# satellites_pcb_v2_0.net
KiCad netlist of a schematic drawn in EAGLE
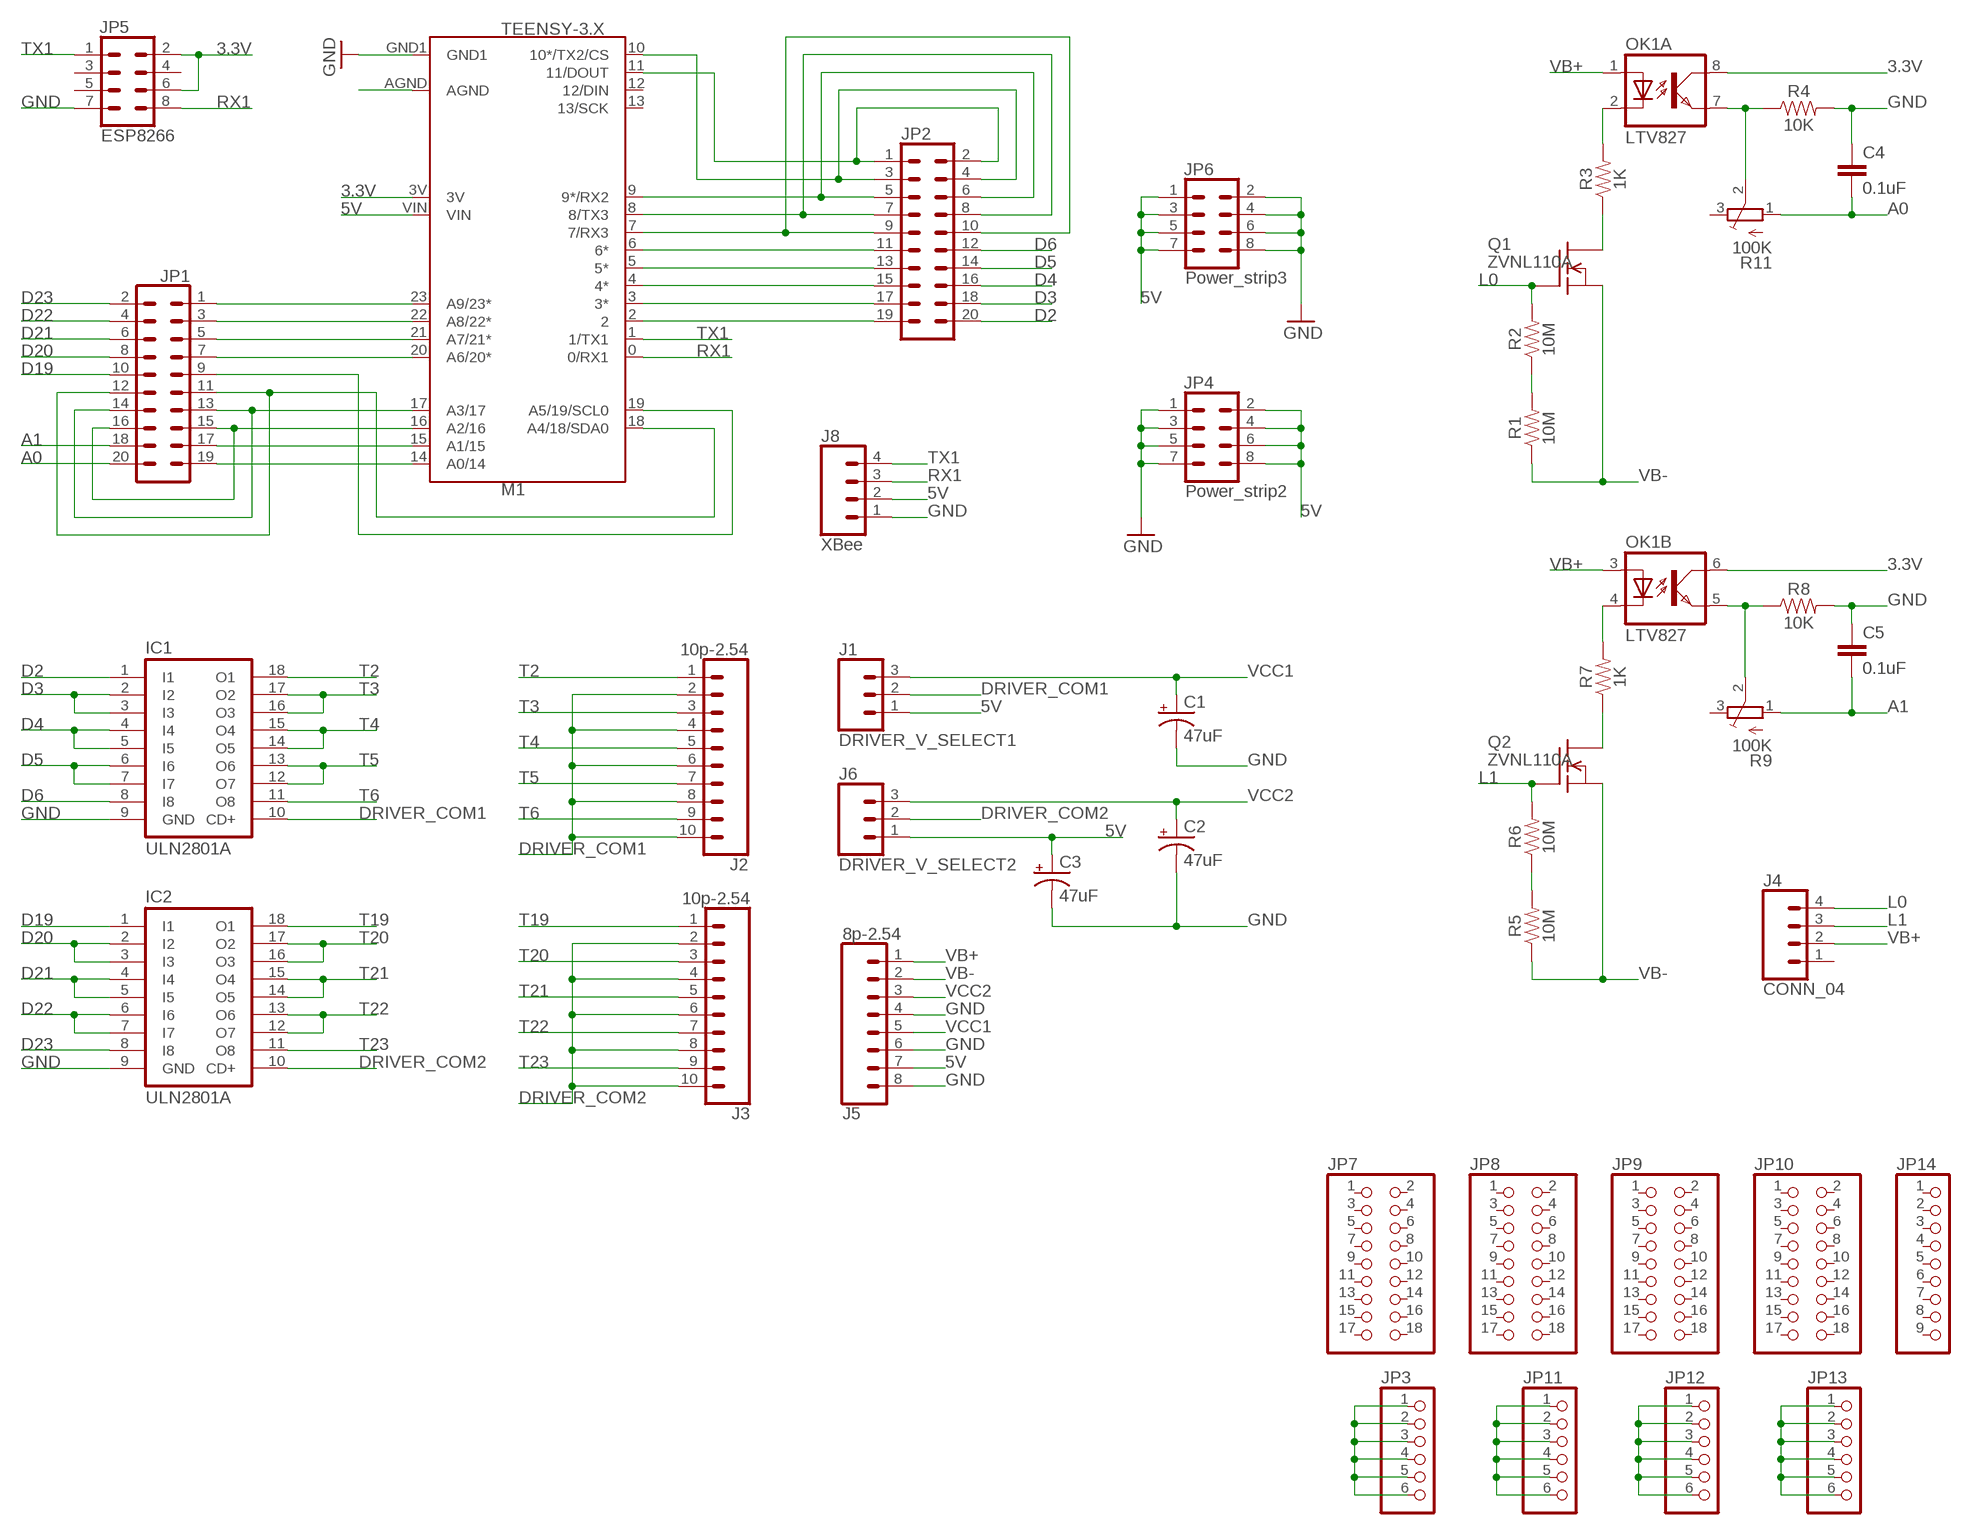
[diagram p0: schematic, sheet 1]

(export (version "E")
  (design (tool "Eeschema 10.0.6"))
  (components
    (comp (ref "C1")
      (value "47uF")
      (footprint "eagle-import:CPOL-RADIAL-2.5MM-6.5MM")
      (libsource (lib "eagle-import") (part "100UF-POLAR-RADIAL-2.5MM-25V-20%"))
    )
    (comp (ref "C2")
      (value "47uF")
      (footprint "eagle-import:CPOL-RADIAL-2.5MM-6.5MM")
      (libsource (lib "eagle-import") (part "100UF-POLAR-RADIAL-2.5MM-25V-20%"))
    )
    (comp (ref "C3")
      (value "47uF")
      (footprint "eagle-import:CPOL-RADIAL-2.5MM-6.5MM")
      (libsource (lib "eagle-import") (part "100UF-POLAR-RADIAL-2.5MM-25V-20%"))
    )
    (comp (ref "C4")
      (value "0.1uF")
      (footprint "eagle-import:CAP-PTH-2.54")
      (libsource (lib "eagle-import") (part "22PF-PTH-2.54MM-200V-5%"))
    )
    (comp (ref "C5")
      (value "0.1uF")
      (footprint "eagle-import:CAP-PTH-2.54")
      (libsource (lib "eagle-import") (part "22PF-PTH-2.54MM-200V-5%"))
    )
    (comp (ref "IC1")
      (value "ULN2801A")
      (footprint "eagle-import:DIL18")
      (libsource (lib "eagle-import") (part "ULN2801A"))
    )
    (comp (ref "IC2")
      (value "ULN2801A")
      (footprint "eagle-import:DIL18")
      (libsource (lib "eagle-import") (part "ULN2801A"))
    )
    (comp (ref "J1")
      (value "DRIVER_V_SELECT1")
      (footprint "eagle-import:1X03_LOCK")
      (libsource (lib "eagle-import") (part "CONN_03LOCK"))
    )
    (comp (ref "J2")
      (value "10p-2.54")
      (footprint "eagle-import:SCREW_TERMINAL_10P_2.54MM_LONGPAD")
      (libsource (lib "eagle-import") (part "CONN_10"))
    )
    (comp (ref "J3")
      (value "10p-2.54")
      (footprint "eagle-import:SCREW_TERMINAL_10P_2.54MM_LONGPAD")
      (libsource (lib "eagle-import") (part "CONN_10"))
    )
    (comp (ref "J4")
      (value "CONN_04")
      (footprint "eagle-import:SCREW_TERMINAL_4P_2.54MM")
      (libsource (lib "eagle-import") (part "CONN_04"))
    )
    (comp (ref "J5")
      (value "8p-2.54")
      (footprint "eagle-import:SCREW_TERMINAL_8P_2.54MM_LONGPAD")
      (libsource (lib "eagle-import") (part "CONN_08SCREW_TERMINAL_8P_2.54MM_LONGPAD"))
    )
    (comp (ref "J6")
      (value "DRIVER_V_SELECT2")
      (footprint "eagle-import:1X03_LOCK")
      (libsource (lib "eagle-import") (part "CONN_03LOCK"))
    )
    (comp (ref "J8")
      (value "XBee")
      (footprint "eagle-import:1X04_LOCK")
      (libsource (lib "eagle-import") (part "CONN_04LOCK"))
    )
    (comp (ref "JP1")
      (value "CONN_10X2")
      (footprint "eagle-import:2X10")
      (libsource (lib "eagle-import") (part "CONN_10X2"))
    )
    (comp (ref "JP2")
      (value "CONN_10X2")
      (footprint "eagle-import:2X10")
      (libsource (lib "eagle-import") (part "CONN_10X2"))
    )
    (comp (ref "JP3")
      (value "PINHD-1X6CLEAN")
      (footprint "eagle-import:1X06-CLEAN")
      (libsource (lib "eagle-import") (part "PINHD-1X6CLEAN"))
    )
    (comp (ref "JP4")
      (value "Power_strip2")
      (footprint "eagle-import:2X4")
      (libsource (lib "eagle-import") (part "CONN_04X2"))
    )
    (comp (ref "JP5")
      (value "ESP8266")
      (footprint "eagle-import:2X4")
      (libsource (lib "eagle-import") (part "CONN_04X2"))
    )
    (comp (ref "JP6")
      (value "Power_strip3")
      (footprint "eagle-import:2X4")
      (libsource (lib "eagle-import") (part "CONN_04X2"))
    )
    (comp (ref "JP7")
      (value "PINHD-2X9-CBIG")
      (footprint "eagle-import:2X09-CLEANBIG")
      (libsource (lib "eagle-import") (part "PINHD-2X9-CBIG"))
    )
    (comp (ref "JP8")
      (value "PINHD-2X9-CBIG")
      (footprint "eagle-import:2X09-CLEANBIG")
      (libsource (lib "eagle-import") (part "PINHD-2X9-CBIG"))
    )
    (comp (ref "JP9")
      (value "PINHD-2X9-CBIG")
      (footprint "eagle-import:2X09-CLEANBIG")
      (libsource (lib "eagle-import") (part "PINHD-2X9-CBIG"))
    )
    (comp (ref "JP10")
      (value "PINHD-2X9-CBIG")
      (footprint "eagle-import:2X09-CLEANBIG")
      (libsource (lib "eagle-import") (part "PINHD-2X9-CBIG"))
    )
    (comp (ref "JP11")
      (value "PINHD-1X6CLEAN")
      (footprint "eagle-import:1X06-CLEAN")
      (libsource (lib "eagle-import") (part "PINHD-1X6CLEAN"))
    )
    (comp (ref "JP12")
      (value "PINHD-1X6CLEAN")
      (footprint "eagle-import:1X06-CLEAN")
      (libsource (lib "eagle-import") (part "PINHD-1X6CLEAN"))
    )
    (comp (ref "JP13")
      (value "PINHD-1X6CLEAN")
      (footprint "eagle-import:1X06-CLEAN")
      (libsource (lib "eagle-import") (part "PINHD-1X6CLEAN"))
    )
    (comp (ref "JP14")
      (value "PINHD-1X9")
      (footprint "eagle-import:1X09-BIG")
      (libsource (lib "eagle-import") (part "PINHD-1X9"))
    )
    (comp (ref "M1")
      (value "TEENSY-3.X")
      (footprint "eagle-import:TEENSY-3.1_NOSILK")
      (libsource (lib "eagle-import") (part "TEENSY-3.1-TWO_ROWSNOSILK"))
    )
    (comp (ref "OK1")
      (value "LTV827")
      (footprint "eagle-import:DIP08")
      (libsource (lib "eagle-import") (part "LTV827"))
    )
    (comp (ref "Q1")
      (value "ZVNL110A")
      (footprint "eagle-import:TO92")
      (libsource (lib "eagle-import") (part "ZVNL110A"))
    )
    (comp (ref "Q2")
      (value "ZVNL110A")
      (footprint "eagle-import:TO92")
      (libsource (lib "eagle-import") (part "ZVNL110A"))
    )
    (comp (ref "R1")
      (value "10M")
      (footprint "eagle-import:AXIAL-0.3")
      (libsource (lib "eagle-import") (part "RESISTORAXIAL-0.3"))
    )
    (comp (ref "R2")
      (value "10M")
      (footprint "eagle-import:AXIAL-0.3")
      (libsource (lib "eagle-import") (part "RESISTORAXIAL-0.3"))
    )
    (comp (ref "R3")
      (value "1K")
      (footprint "eagle-import:AXIAL-0.3")
      (libsource (lib "eagle-import") (part "RESISTORAXIAL-0.3"))
    )
    (comp (ref "R4")
      (value "10K")
      (footprint "eagle-import:AXIAL-0.3")
      (libsource (lib "eagle-import") (part "RESISTORAXIAL-0.3"))
    )
    (comp (ref "R5")
      (value "10M")
      (footprint "eagle-import:AXIAL-0.3")
      (libsource (lib "eagle-import") (part "RESISTORAXIAL-0.3"))
    )
    (comp (ref "R6")
      (value "10M")
      (footprint "eagle-import:AXIAL-0.3")
      (libsource (lib "eagle-import") (part "RESISTORAXIAL-0.3"))
    )
    (comp (ref "R7")
      (value "1K")
      (footprint "eagle-import:AXIAL-0.3")
      (libsource (lib "eagle-import") (part "RESISTORAXIAL-0.3"))
    )
    (comp (ref "R8")
      (value "10K")
      (footprint "eagle-import:AXIAL-0.3")
      (libsource (lib "eagle-import") (part "RESISTORAXIAL-0.3"))
    )
    (comp (ref "R9")
      (value "100K")
      (footprint "eagle-import:TRIM-3386H")
      (libsource (lib "eagle-import") (part "TRIMPOT3386H"))
    )
    (comp (ref "R11")
      (value "100K")
      (footprint "eagle-import:TRIM-3386H")
      (libsource (lib "eagle-import") (part "TRIMPOT3386H"))
    )
  )
  (nets
    (net (code "1") (name "/3.3V") (class "Default")
      (node (ref "JP5") (pin "2") (pinfunction "2_2") (pintype "passive"))
      (node (ref "JP5") (pin "6") (pinfunction "6_6") (pintype "passive"))
      (node (ref "M1") (pin "3V") (pinfunction "3V_3V") (pintype "power_in"))
      (node (ref "OK1") (pin "6") (pinfunction "COL_6") (pintype "passive"))
      (node (ref "OK1") (pin "8") (pinfunction "COL_8") (pintype "passive"))
    )
    (net (code "2") (name "/5V") (class "Default")
      (node (ref "C3") (pin "1") (pinfunction "+_1") (pintype "passive"))
      (node (ref "J1") (pin "1") (pinfunction "1_1") (pintype "passive"))
      (node (ref "J5") (pin "7") (pinfunction "7_7") (pintype "passive"))
      (node (ref "J6") (pin "1") (pinfunction "1_1") (pintype "passive"))
      (node (ref "J8") (pin "2") (pinfunction "2_2") (pintype "passive"))
      (node (ref "JP4") (pin "2") (pinfunction "2_2") (pintype "passive"))
      (node (ref "JP4") (pin "4") (pinfunction "4_4") (pintype "passive"))
      (node (ref "JP4") (pin "6") (pinfunction "6_6") (pintype "passive"))
      (node (ref "JP4") (pin "8") (pinfunction "8_8") (pintype "passive"))
      (node (ref "JP6") (pin "1") (pinfunction "1_1") (pintype "passive"))
      (node (ref "JP6") (pin "3") (pinfunction "3_3") (pintype "passive"))
      (node (ref "JP6") (pin "5") (pinfunction "5_5") (pintype "passive"))
      (node (ref "JP6") (pin "7") (pinfunction "7_7") (pintype "passive"))
      (node (ref "M1") (pin "VIN") (pinfunction "VIN_VIN") (pintype "power_in"))
    )
    (net (code "3") (name "/A0") (class "Default")
      (node (ref "C4") (pin "2") (pinfunction "2_2") (pintype "passive"))
      (node (ref "JP1") (pin "20") (pinfunction "20_20") (pintype "passive"))
      (node (ref "R11") (pin "1") (pinfunction "A_1") (pintype "passive"))
    )
    (net (code "4") (name "/A1") (class "Default")
      (node (ref "C5") (pin "2") (pinfunction "2_2") (pintype "passive"))
      (node (ref "JP1") (pin "18") (pinfunction "18_18") (pintype "passive"))
      (node (ref "R9") (pin "1") (pinfunction "A_1") (pintype "passive"))
    )
    (net (code "5") (name "/D2") (class "Default")
      (node (ref "IC1") (pin "1") (pinfunction "I1_1") (pintype "input"))
      (node (ref "JP2") (pin "20") (pinfunction "20_20") (pintype "passive"))
    )
    (net (code "6") (name "/D3") (class "Default")
      (node (ref "IC1") (pin "2") (pinfunction "I2_2") (pintype "input"))
      (node (ref "IC1") (pin "3") (pinfunction "I3_3") (pintype "input"))
      (node (ref "JP2") (pin "18") (pinfunction "18_18") (pintype "passive"))
    )
    (net (code "7") (name "/D4") (class "Default")
      (node (ref "IC1") (pin "4") (pinfunction "I4_4") (pintype "input"))
      (node (ref "IC1") (pin "5") (pinfunction "I5_5") (pintype "input"))
      (node (ref "JP2") (pin "16") (pinfunction "16_16") (pintype "passive"))
    )
    (net (code "8") (name "/D5") (class "Default")
      (node (ref "IC1") (pin "6") (pinfunction "I6_6") (pintype "input"))
      (node (ref "IC1") (pin "7") (pinfunction "I7_7") (pintype "input"))
      (node (ref "JP2") (pin "14") (pinfunction "14_14") (pintype "passive"))
    )
    (net (code "9") (name "/D6") (class "Default")
      (node (ref "IC1") (pin "8") (pinfunction "I8_8") (pintype "input"))
      (node (ref "JP2") (pin "12") (pinfunction "12_12") (pintype "passive"))
    )
    (net (code "10") (name "/D19") (class "Default")
      (node (ref "IC2") (pin "1") (pinfunction "I1_1") (pintype "input"))
      (node (ref "JP1") (pin "10") (pinfunction "10_10") (pintype "passive"))
    )
    (net (code "11") (name "/D20") (class "Default")
      (node (ref "IC2") (pin "2") (pinfunction "I2_2") (pintype "input"))
      (node (ref "IC2") (pin "3") (pinfunction "I3_3") (pintype "input"))
      (node (ref "JP1") (pin "8") (pinfunction "8_8") (pintype "passive"))
    )
    (net (code "12") (name "/D21") (class "Default")
      (node (ref "IC2") (pin "4") (pinfunction "I4_4") (pintype "input"))
      (node (ref "IC2") (pin "5") (pinfunction "I5_5") (pintype "input"))
      (node (ref "JP1") (pin "6") (pinfunction "6_6") (pintype "passive"))
    )
    (net (code "13") (name "/D22") (class "Default")
      (node (ref "IC2") (pin "6") (pinfunction "I6_6") (pintype "input"))
      (node (ref "IC2") (pin "7") (pinfunction "I7_7") (pintype "input"))
      (node (ref "JP1") (pin "4") (pinfunction "4_4") (pintype "passive"))
    )
    (net (code "14") (name "/D23") (class "Default")
      (node (ref "IC2") (pin "8") (pinfunction "I8_8") (pintype "input"))
      (node (ref "JP1") (pin "2") (pinfunction "2_2") (pintype "passive"))
    )
    (net (code "15") (name "/DRIVER_COM1") (class "Default")
      (node (ref "IC1") (pin "10") (pinfunction "CD+_10") (pintype "passive"))
      (node (ref "J1") (pin "2") (pinfunction "2_2") (pintype "passive"))
      (node (ref "J2") (pin "10") (pinfunction "10_10") (pintype "passive"))
      (node (ref "J2") (pin "2") (pinfunction "2_2") (pintype "passive"))
      (node (ref "J2") (pin "4") (pinfunction "4_4") (pintype "passive"))
      (node (ref "J2") (pin "6") (pinfunction "6_6") (pintype "passive"))
      (node (ref "J2") (pin "8") (pinfunction "8_8") (pintype "passive"))
    )
    (net (code "16") (name "/DRIVER_COM2") (class "Default")
      (node (ref "IC2") (pin "10") (pinfunction "CD+_10") (pintype "passive"))
      (node (ref "J3") (pin "10") (pinfunction "10_10") (pintype "passive"))
      (node (ref "J3") (pin "2") (pinfunction "2_2") (pintype "passive"))
      (node (ref "J3") (pin "4") (pinfunction "4_4") (pintype "passive"))
      (node (ref "J3") (pin "6") (pinfunction "6_6") (pintype "passive"))
      (node (ref "J3") (pin "8") (pinfunction "8_8") (pintype "passive"))
      (node (ref "J6") (pin "2") (pinfunction "2_2") (pintype "passive"))
    )
    (net (code "17") (name "/L0") (class "Default")
      (node (ref "J4") (pin "4") (pinfunction "4_4") (pintype "passive"))
      (node (ref "Q1") (pin "2") (pinfunction "G_2") (pintype "passive"))
      (node (ref "R2") (pin "P$2") (pinfunction "2_P$2") (pintype "passive"))
    )
    (net (code "18") (name "/L1") (class "Default")
      (node (ref "J4") (pin "3") (pinfunction "3_3") (pintype "passive"))
      (node (ref "Q2") (pin "2") (pinfunction "G_2") (pintype "passive"))
      (node (ref "R6") (pin "P$2") (pinfunction "2_P$2") (pintype "passive"))
    )
    (net (code "19") (name "/RX1") (class "Default")
      (node (ref "J8") (pin "3") (pinfunction "3_3") (pintype "passive"))
      (node (ref "JP5") (pin "8") (pinfunction "8_8") (pintype "passive"))
      (node (ref "M1") (pin "0") (pinfunction "0/RX1_0") (pintype "bidirectional"))
    )
    (net (code "20") (name "/T2") (class "Default")
      (node (ref "IC1") (pin "18") (pinfunction "O1_18") (pintype "open_collector"))
      (node (ref "J2") (pin "1") (pinfunction "1_1") (pintype "passive"))
    )
    (net (code "21") (name "/T3") (class "Default")
      (node (ref "IC1") (pin "16") (pinfunction "O3_16") (pintype "open_collector"))
      (node (ref "IC1") (pin "17") (pinfunction "O2_17") (pintype "open_collector"))
      (node (ref "J2") (pin "3") (pinfunction "3_3") (pintype "passive"))
    )
    (net (code "22") (name "/T4") (class "Default")
      (node (ref "IC1") (pin "14") (pinfunction "O5_14") (pintype "open_collector"))
      (node (ref "IC1") (pin "15") (pinfunction "O4_15") (pintype "open_collector"))
      (node (ref "J2") (pin "5") (pinfunction "5_5") (pintype "passive"))
    )
    (net (code "23") (name "/T5") (class "Default")
      (node (ref "IC1") (pin "12") (pinfunction "O7_12") (pintype "open_collector"))
      (node (ref "IC1") (pin "13") (pinfunction "O6_13") (pintype "open_collector"))
      (node (ref "J2") (pin "7") (pinfunction "7_7") (pintype "passive"))
    )
    (net (code "24") (name "/T6") (class "Default")
      (node (ref "IC1") (pin "11") (pinfunction "O8_11") (pintype "open_collector"))
      (node (ref "J2") (pin "9") (pinfunction "9_9") (pintype "passive"))
    )
    (net (code "25") (name "/T19") (class "Default")
      (node (ref "IC2") (pin "18") (pinfunction "O1_18") (pintype "open_collector"))
      (node (ref "J3") (pin "1") (pinfunction "1_1") (pintype "passive"))
    )
    (net (code "26") (name "/T20") (class "Default")
      (node (ref "IC2") (pin "16") (pinfunction "O3_16") (pintype "open_collector"))
      (node (ref "IC2") (pin "17") (pinfunction "O2_17") (pintype "open_collector"))
      (node (ref "J3") (pin "3") (pinfunction "3_3") (pintype "passive"))
    )
    (net (code "27") (name "/T21") (class "Default")
      (node (ref "IC2") (pin "14") (pinfunction "O5_14") (pintype "open_collector"))
      (node (ref "IC2") (pin "15") (pinfunction "O4_15") (pintype "open_collector"))
      (node (ref "J3") (pin "5") (pinfunction "5_5") (pintype "passive"))
    )
    (net (code "28") (name "/T22") (class "Default")
      (node (ref "IC2") (pin "12") (pinfunction "O7_12") (pintype "open_collector"))
      (node (ref "IC2") (pin "13") (pinfunction "O6_13") (pintype "open_collector"))
      (node (ref "J3") (pin "7") (pinfunction "7_7") (pintype "passive"))
    )
    (net (code "29") (name "/T23") (class "Default")
      (node (ref "IC2") (pin "11") (pinfunction "O8_11") (pintype "open_collector"))
      (node (ref "J3") (pin "9") (pinfunction "9_9") (pintype "passive"))
    )
    (net (code "30") (name "/TX1") (class "Default")
      (node (ref "J8") (pin "4") (pinfunction "4_4") (pintype "passive"))
      (node (ref "JP5") (pin "1") (pinfunction "1_1") (pintype "passive"))
      (node (ref "M1") (pin "1") (pinfunction "1/TX1_1") (pintype "bidirectional"))
    )
    (net (code "31") (name "/VB+") (class "Default")
      (node (ref "J4") (pin "2") (pinfunction "2_2") (pintype "passive"))
      (node (ref "J5") (pin "1") (pinfunction "1_1") (pintype "passive"))
      (node (ref "OK1") (pin "1") (pinfunction "A_1") (pintype "passive"))
      (node (ref "OK1") (pin "3") (pinfunction "A_3") (pintype "passive"))
    )
    (net (code "32") (name "/VB-") (class "Default")
      (node (ref "J5") (pin "2") (pinfunction "2_2") (pintype "passive"))
      (node (ref "Q1") (pin "3") (pinfunction "S_3") (pintype "passive"))
      (node (ref "Q2") (pin "3") (pinfunction "S_3") (pintype "passive"))
      (node (ref "R1") (pin "P$1") (pinfunction "1_P$1") (pintype "passive"))
      (node (ref "R5") (pin "P$1") (pinfunction "1_P$1") (pintype "passive"))
    )
    (net (code "33") (name "/VCC1") (class "Default")
      (node (ref "C1") (pin "1") (pinfunction "+_1") (pintype "passive"))
      (node (ref "J1") (pin "3") (pinfunction "3_3") (pintype "passive"))
      (node (ref "J5") (pin "5") (pinfunction "5_5") (pintype "passive"))
    )
    (net (code "34") (name "/VCC2") (class "Default")
      (node (ref "C2") (pin "1") (pinfunction "+_1") (pintype "passive"))
      (node (ref "J5") (pin "3") (pinfunction "3_3") (pintype "passive"))
      (node (ref "J6") (pin "3") (pinfunction "3_3") (pintype "passive"))
    )
    (net (code "35") (name "GND") (class "Default")
      (node (ref "C1") (pin "2") (pinfunction "-_2") (pintype "passive"))
      (node (ref "C2") (pin "2") (pinfunction "-_2") (pintype "passive"))
      (node (ref "C3") (pin "2") (pinfunction "-_2") (pintype "passive"))
      (node (ref "C4") (pin "1") (pinfunction "1_1") (pintype "passive"))
      (node (ref "C5") (pin "1") (pinfunction "1_1") (pintype "passive"))
      (node (ref "IC1") (pin "9") (pinfunction "GND_9") (pintype "power_in"))
      (node (ref "IC2") (pin "9") (pinfunction "GND_9") (pintype "power_in"))
      (node (ref "J5") (pin "4") (pinfunction "4_4") (pintype "passive"))
      (node (ref "J5") (pin "6") (pinfunction "6_6") (pintype "passive"))
      (node (ref "J5") (pin "8") (pinfunction "8_8") (pintype "passive"))
      (node (ref "J8") (pin "1") (pinfunction "1_1") (pintype "passive"))
      (node (ref "JP4") (pin "1") (pinfunction "1_1") (pintype "passive"))
      (node (ref "JP4") (pin "3") (pinfunction "3_3") (pintype "passive"))
      (node (ref "JP4") (pin "5") (pinfunction "5_5") (pintype "passive"))
      (node (ref "JP4") (pin "7") (pinfunction "7_7") (pintype "passive"))
      (node (ref "JP5") (pin "7") (pinfunction "7_7") (pintype "passive"))
      (node (ref "JP6") (pin "2") (pinfunction "2_2") (pintype "passive"))
      (node (ref "JP6") (pin "4") (pinfunction "4_4") (pintype "passive"))
      (node (ref "JP6") (pin "6") (pinfunction "6_6") (pintype "passive"))
      (node (ref "JP6") (pin "8") (pinfunction "8_8") (pintype "passive"))
      (node (ref "M1") (pin "GND1") (pinfunction "GND1_GND1") (pintype "power_in"))
      (node (ref "R4") (pin "P$2") (pinfunction "2_P$2") (pintype "passive"))
      (node (ref "R8") (pin "P$2") (pinfunction "2_P$2") (pintype "passive"))
    )
    (net (code "36") (name "Net-(JP2-Pad19)") (class "Default")
      (node (ref "JP2") (pin "19") (pinfunction "19_19") (pintype "passive"))
      (node (ref "M1") (pin "2") (pinfunction "2_2") (pintype "bidirectional"))
    )
    (net (code "37") (name "Net-(JP3-Pad1)") (class "Default")
      (node (ref "JP3") (pin "1") (pinfunction "1_1") (pintype "passive"))
      (node (ref "JP3") (pin "2") (pinfunction "2_2") (pintype "passive"))
      (node (ref "JP3") (pin "3") (pinfunction "3_3") (pintype "passive"))
      (node (ref "JP3") (pin "4") (pinfunction "4_4") (pintype "passive"))
      (node (ref "JP3") (pin "5") (pinfunction "5_5") (pintype "passive"))
      (node (ref "JP3") (pin "6") (pinfunction "6_6") (pintype "passive"))
    )
    (net (code "38") (name "Net-(JP11-Pad1)") (class "Default")
      (node (ref "JP11") (pin "1") (pinfunction "1_1") (pintype "passive"))
      (node (ref "JP11") (pin "2") (pinfunction "2_2") (pintype "passive"))
      (node (ref "JP11") (pin "3") (pinfunction "3_3") (pintype "passive"))
      (node (ref "JP11") (pin "4") (pinfunction "4_4") (pintype "passive"))
      (node (ref "JP11") (pin "5") (pinfunction "5_5") (pintype "passive"))
      (node (ref "JP11") (pin "6") (pinfunction "6_6") (pintype "passive"))
    )
    (net (code "39") (name "Net-(JP12-Pad1)") (class "Default")
      (node (ref "JP12") (pin "1") (pinfunction "1_1") (pintype "passive"))
      (node (ref "JP12") (pin "2") (pinfunction "2_2") (pintype "passive"))
      (node (ref "JP12") (pin "3") (pinfunction "3_3") (pintype "passive"))
      (node (ref "JP12") (pin "4") (pinfunction "4_4") (pintype "passive"))
      (node (ref "JP12") (pin "5") (pinfunction "5_5") (pintype "passive"))
      (node (ref "JP12") (pin "6") (pinfunction "6_6") (pintype "passive"))
    )
    (net (code "40") (name "Net-(JP13-Pad1)") (class "Default")
      (node (ref "JP13") (pin "1") (pinfunction "1_1") (pintype "passive"))
      (node (ref "JP13") (pin "2") (pinfunction "2_2") (pintype "passive"))
      (node (ref "JP13") (pin "3") (pinfunction "3_3") (pintype "passive"))
      (node (ref "JP13") (pin "4") (pinfunction "4_4") (pintype "passive"))
      (node (ref "JP13") (pin "5") (pinfunction "5_5") (pintype "passive"))
      (node (ref "JP13") (pin "6") (pinfunction "6_6") (pintype "passive"))
    )
    (net (code "41") (name "Net-(M1-3*)") (class "Default")
      (node (ref "JP2") (pin "17") (pinfunction "17_17") (pintype "passive"))
      (node (ref "M1") (pin "3") (pinfunction "3*_3") (pintype "bidirectional"))
    )
    (net (code "42") (name "Net-(M1-4*)") (class "Default")
      (node (ref "JP2") (pin "15") (pinfunction "15_15") (pintype "passive"))
      (node (ref "M1") (pin "4") (pinfunction "4*_4") (pintype "bidirectional"))
    )
    (net (code "43") (name "Net-(M1-5*)") (class "Default")
      (node (ref "JP2") (pin "13") (pinfunction "13_13") (pintype "passive"))
      (node (ref "M1") (pin "5") (pinfunction "5*_5") (pintype "bidirectional"))
    )
    (net (code "44") (name "Net-(M1-6*)") (class "Default")
      (node (ref "JP2") (pin "11") (pinfunction "11_11") (pintype "passive"))
      (node (ref "M1") (pin "6") (pinfunction "6*_6") (pintype "bidirectional"))
    )
    (net (code "45") (name "Net-(M1-7{slash}RX3)") (class "Default")
      (node (ref "JP2") (pin "10") (pinfunction "10_10") (pintype "passive"))
      (node (ref "JP2") (pin "9") (pinfunction "9_9") (pintype "passive"))
      (node (ref "M1") (pin "7") (pinfunction "7/RX3_7") (pintype "bidirectional"))
    )
    (net (code "46") (name "Net-(M1-8{slash}TX3)") (class "Default")
      (node (ref "JP2") (pin "7") (pinfunction "7_7") (pintype "passive"))
      (node (ref "JP2") (pin "8") (pinfunction "8_8") (pintype "passive"))
      (node (ref "M1") (pin "8") (pinfunction "8/TX3_8") (pintype "bidirectional"))
    )
    (net (code "47") (name "Net-(M1-9*{slash}RX2)") (class "Default")
      (node (ref "JP2") (pin "5") (pinfunction "5_5") (pintype "passive"))
      (node (ref "JP2") (pin "6") (pinfunction "6_6") (pintype "passive"))
      (node (ref "M1") (pin "9") (pinfunction "9*/RX2_9") (pintype "bidirectional"))
    )
    (net (code "48") (name "Net-(M1-10*{slash}TX2{slash}CS)") (class "Default")
      (node (ref "JP2") (pin "3") (pinfunction "3_3") (pintype "passive"))
      (node (ref "JP2") (pin "4") (pinfunction "4_4") (pintype "passive"))
      (node (ref "M1") (pin "10") (pinfunction "10*/TX2/CS_10") (pintype "bidirectional"))
    )
    (net (code "49") (name "Net-(M1-11{slash}DOUT)") (class "Default")
      (node (ref "JP2") (pin "1") (pinfunction "1_1") (pintype "passive"))
      (node (ref "JP2") (pin "2") (pinfunction "2_2") (pintype "passive"))
      (node (ref "M1") (pin "11") (pinfunction "11/DOUT_11") (pintype "bidirectional"))
    )
    (net (code "50") (name "Net-(M1-A0{slash}14)") (class "Default")
      (node (ref "JP1") (pin "19") (pinfunction "19_19") (pintype "passive"))
      (node (ref "M1") (pin "14") (pinfunction "A0/14_14") (pintype "bidirectional"))
    )
    (net (code "51") (name "Net-(M1-A1{slash}15)") (class "Default")
      (node (ref "JP1") (pin "17") (pinfunction "17_17") (pintype "passive"))
      (node (ref "M1") (pin "15") (pinfunction "A1/15_15") (pintype "bidirectional"))
    )
    (net (code "52") (name "Net-(M1-A2{slash}16)") (class "Default")
      (node (ref "JP1") (pin "15") (pinfunction "15_15") (pintype "passive"))
      (node (ref "JP1") (pin "16") (pinfunction "16_16") (pintype "passive"))
      (node (ref "M1") (pin "16") (pinfunction "A2/16_16") (pintype "bidirectional"))
    )
    (net (code "53") (name "Net-(M1-A3{slash}17)") (class "Default")
      (node (ref "JP1") (pin "13") (pinfunction "13_13") (pintype "passive"))
      (node (ref "JP1") (pin "14") (pinfunction "14_14") (pintype "passive"))
      (node (ref "M1") (pin "17") (pinfunction "A3/17_17") (pintype "bidirectional"))
    )
    (net (code "54") (name "Net-(M1-A4{slash}18{slash}SDA0)") (class "Default")
      (node (ref "JP1") (pin "11") (pinfunction "11_11") (pintype "passive"))
      (node (ref "JP1") (pin "12") (pinfunction "12_12") (pintype "passive"))
      (node (ref "M1") (pin "18") (pinfunction "A4/18/SDA0_18") (pintype "bidirectional"))
    )
    (net (code "55") (name "Net-(M1-A5{slash}19{slash}SCL0)") (class "Default")
      (node (ref "JP1") (pin "9") (pinfunction "9_9") (pintype "passive"))
      (node (ref "M1") (pin "19") (pinfunction "A5/19/SCL0_19") (pintype "bidirectional"))
    )
    (net (code "56") (name "Net-(M1-A6{slash}20*)") (class "Default")
      (node (ref "JP1") (pin "7") (pinfunction "7_7") (pintype "passive"))
      (node (ref "M1") (pin "20") (pinfunction "A6/20*_20") (pintype "bidirectional"))
    )
    (net (code "57") (name "Net-(M1-A7{slash}21*)") (class "Default")
      (node (ref "JP1") (pin "5") (pinfunction "5_5") (pintype "passive"))
      (node (ref "M1") (pin "21") (pinfunction "A7/21*_21") (pintype "bidirectional"))
    )
    (net (code "58") (name "Net-(M1-A8{slash}22*)") (class "Default")
      (node (ref "JP1") (pin "3") (pinfunction "3_3") (pintype "passive"))
      (node (ref "M1") (pin "22") (pinfunction "A8/22*_22") (pintype "bidirectional"))
    )
    (net (code "59") (name "Net-(M1-A9{slash}23*)") (class "Default")
      (node (ref "JP1") (pin "1") (pinfunction "1_1") (pintype "passive"))
      (node (ref "M1") (pin "23") (pinfunction "A9/23*_23") (pintype "bidirectional"))
    )
    (net (code "60") (name "Net-(OK1A-C)") (class "Default")
      (node (ref "OK1") (pin "2") (pinfunction "C_2") (pintype "passive"))
      (node (ref "R3") (pin "P$2") (pinfunction "2_P$2") (pintype "passive"))
    )
    (net (code "61") (name "Net-(OK1A-EMIT)") (class "Default")
      (node (ref "OK1") (pin "7") (pinfunction "EMIT_7") (pintype "passive"))
      (node (ref "R11") (pin "2") (pinfunction "S_2") (pintype "passive"))
      (node (ref "R4") (pin "P$1") (pinfunction "1_P$1") (pintype "passive"))
    )
    (net (code "62") (name "Net-(OK1B-C)") (class "Default")
      (node (ref "OK1") (pin "4") (pinfunction "C_4") (pintype "passive"))
      (node (ref "R7") (pin "P$2") (pinfunction "2_P$2") (pintype "passive"))
    )
    (net (code "63") (name "Net-(OK1B-EMIT)") (class "Default")
      (node (ref "OK1") (pin "5") (pinfunction "EMIT_5") (pintype "passive"))
      (node (ref "R8") (pin "P$1") (pinfunction "1_P$1") (pintype "passive"))
      (node (ref "R9") (pin "2") (pinfunction "S_2") (pintype "passive"))
    )
    (net (code "64") (name "Net-(Q1-D)") (class "Default")
      (node (ref "Q1") (pin "1") (pinfunction "D_1") (pintype "passive"))
      (node (ref "R3") (pin "P$1") (pinfunction "1_P$1") (pintype "passive"))
    )
    (net (code "65") (name "Net-(Q2-D)") (class "Default")
      (node (ref "Q2") (pin "1") (pinfunction "D_1") (pintype "passive"))
      (node (ref "R7") (pin "P$1") (pinfunction "1_P$1") (pintype "passive"))
    )
    (net (code "66") (name "Net-(R1-2)") (class "Default")
      (node (ref "R1") (pin "P$2") (pinfunction "2_P$2") (pintype "passive"))
      (node (ref "R2") (pin "P$1") (pinfunction "1_P$1") (pintype "passive"))
    )
    (net (code "67") (name "Net-(R5-2)") (class "Default")
      (node (ref "R5") (pin "P$2") (pinfunction "2_P$2") (pintype "passive"))
      (node (ref "R6") (pin "P$1") (pinfunction "1_P$1") (pintype "passive"))
    )
    (net (code "68") (name "unconnected-(J4-Pad1)") (class "Default")
      (node (ref "J4") (pin "1") (pinfunction "1_1") (pintype "passive"))
    )
    (net (code "69") (name "unconnected-(JP5-Pad3)") (class "Default")
      (node (ref "JP5") (pin "3") (pinfunction "3_3") (pintype "passive"))
    )
    (net (code "70") (name "unconnected-(JP5-Pad4)") (class "Default")
      (node (ref "JP5") (pin "4") (pinfunction "4_4") (pintype "passive"))
    )
    (net (code "71") (name "unconnected-(JP5-Pad5)") (class "Default")
      (node (ref "JP5") (pin "5") (pinfunction "5_5") (pintype "passive"))
    )
    (net (code "72") (name "unconnected-(JP7-Pad1)") (class "Default")
      (node (ref "JP7") (pin "1") (pinfunction "1_1") (pintype "passive"))
    )
    (net (code "73") (name "unconnected-(JP7-Pad2)") (class "Default")
      (node (ref "JP7") (pin "2") (pinfunction "2_2") (pintype "passive"))
    )
    (net (code "74") (name "unconnected-(JP7-Pad3)") (class "Default")
      (node (ref "JP7") (pin "3") (pinfunction "3_3") (pintype "passive"))
    )
    (net (code "75") (name "unconnected-(JP7-Pad4)") (class "Default")
      (node (ref "JP7") (pin "4") (pinfunction "4_4") (pintype "passive"))
    )
    (net (code "76") (name "unconnected-(JP7-Pad5)") (class "Default")
      (node (ref "JP7") (pin "5") (pinfunction "5_5") (pintype "passive"))
    )
    (net (code "77") (name "unconnected-(JP7-Pad6)") (class "Default")
      (node (ref "JP7") (pin "6") (pinfunction "6_6") (pintype "passive"))
    )
    (net (code "78") (name "unconnected-(JP7-Pad7)") (class "Default")
      (node (ref "JP7") (pin "7") (pinfunction "7_7") (pintype "passive"))
    )
    (net (code "79") (name "unconnected-(JP7-Pad8)") (class "Default")
      (node (ref "JP7") (pin "8") (pinfunction "8_8") (pintype "passive"))
    )
    (net (code "80") (name "unconnected-(JP7-Pad9)") (class "Default")
      (node (ref "JP7") (pin "9") (pinfunction "9_9") (pintype "passive"))
    )
    (net (code "81") (name "unconnected-(JP7-Pad10)") (class "Default")
      (node (ref "JP7") (pin "10") (pinfunction "10_10") (pintype "passive"))
    )
    (net (code "82") (name "unconnected-(JP7-Pad11)") (class "Default")
      (node (ref "JP7") (pin "11") (pinfunction "11_11") (pintype "passive"))
    )
    (net (code "83") (name "unconnected-(JP7-Pad12)") (class "Default")
      (node (ref "JP7") (pin "12") (pinfunction "12_12") (pintype "passive"))
    )
    (net (code "84") (name "unconnected-(JP7-Pad13)") (class "Default")
      (node (ref "JP7") (pin "13") (pinfunction "13_13") (pintype "passive"))
    )
    (net (code "85") (name "unconnected-(JP7-Pad14)") (class "Default")
      (node (ref "JP7") (pin "14") (pinfunction "14_14") (pintype "passive"))
    )
    (net (code "86") (name "unconnected-(JP7-Pad15)") (class "Default")
      (node (ref "JP7") (pin "15") (pinfunction "15_15") (pintype "passive"))
    )
    (net (code "87") (name "unconnected-(JP7-Pad16)") (class "Default")
      (node (ref "JP7") (pin "16") (pinfunction "16_16") (pintype "passive"))
    )
    (net (code "88") (name "unconnected-(JP7-Pad17)") (class "Default")
      (node (ref "JP7") (pin "17") (pinfunction "17_17") (pintype "passive"))
    )
    (net (code "89") (name "unconnected-(JP7-Pad18)") (class "Default")
      (node (ref "JP7") (pin "18") (pinfunction "18_18") (pintype "passive"))
    )
    (net (code "90") (name "unconnected-(JP8-Pad1)") (class "Default")
      (node (ref "JP8") (pin "1") (pinfunction "1_1") (pintype "passive"))
    )
    (net (code "91") (name "unconnected-(JP8-Pad2)") (class "Default")
      (node (ref "JP8") (pin "2") (pinfunction "2_2") (pintype "passive"))
    )
    (net (code "92") (name "unconnected-(JP8-Pad3)") (class "Default")
      (node (ref "JP8") (pin "3") (pinfunction "3_3") (pintype "passive"))
    )
    (net (code "93") (name "unconnected-(JP8-Pad4)") (class "Default")
      (node (ref "JP8") (pin "4") (pinfunction "4_4") (pintype "passive"))
    )
    (net (code "94") (name "unconnected-(JP8-Pad5)") (class "Default")
      (node (ref "JP8") (pin "5") (pinfunction "5_5") (pintype "passive"))
    )
    (net (code "95") (name "unconnected-(JP8-Pad6)") (class "Default")
      (node (ref "JP8") (pin "6") (pinfunction "6_6") (pintype "passive"))
    )
    (net (code "96") (name "unconnected-(JP8-Pad7)") (class "Default")
      (node (ref "JP8") (pin "7") (pinfunction "7_7") (pintype "passive"))
    )
    (net (code "97") (name "unconnected-(JP8-Pad8)") (class "Default")
      (node (ref "JP8") (pin "8") (pinfunction "8_8") (pintype "passive"))
    )
    (net (code "98") (name "unconnected-(JP8-Pad9)") (class "Default")
      (node (ref "JP8") (pin "9") (pinfunction "9_9") (pintype "passive"))
    )
    (net (code "99") (name "unconnected-(JP8-Pad10)") (class "Default")
      (node (ref "JP8") (pin "10") (pinfunction "10_10") (pintype "passive"))
    )
    (net (code "100") (name "unconnected-(JP8-Pad11)") (class "Default")
      (node (ref "JP8") (pin "11") (pinfunction "11_11") (pintype "passive"))
    )
    (net (code "101") (name "unconnected-(JP8-Pad12)") (class "Default")
      (node (ref "JP8") (pin "12") (pinfunction "12_12") (pintype "passive"))
    )
    (net (code "102") (name "unconnected-(JP8-Pad13)") (class "Default")
      (node (ref "JP8") (pin "13") (pinfunction "13_13") (pintype "passive"))
    )
    (net (code "103") (name "unconnected-(JP8-Pad14)") (class "Default")
      (node (ref "JP8") (pin "14") (pinfunction "14_14") (pintype "passive"))
    )
    (net (code "104") (name "unconnected-(JP8-Pad15)") (class "Default")
      (node (ref "JP8") (pin "15") (pinfunction "15_15") (pintype "passive"))
    )
    (net (code "105") (name "unconnected-(JP8-Pad16)") (class "Default")
      (node (ref "JP8") (pin "16") (pinfunction "16_16") (pintype "passive"))
    )
    (net (code "106") (name "unconnected-(JP8-Pad17)") (class "Default")
      (node (ref "JP8") (pin "17") (pinfunction "17_17") (pintype "passive"))
    )
    (net (code "107") (name "unconnected-(JP8-Pad18)") (class "Default")
      (node (ref "JP8") (pin "18") (pinfunction "18_18") (pintype "passive"))
    )
    (net (code "108") (name "unconnected-(JP9-Pad1)") (class "Default")
      (node (ref "JP9") (pin "1") (pinfunction "1_1") (pintype "passive"))
    )
    (net (code "109") (name "unconnected-(JP9-Pad2)") (class "Default")
      (node (ref "JP9") (pin "2") (pinfunction "2_2") (pintype "passive"))
    )
    (net (code "110") (name "unconnected-(JP9-Pad3)") (class "Default")
      (node (ref "JP9") (pin "3") (pinfunction "3_3") (pintype "passive"))
    )
    (net (code "111") (name "unconnected-(JP9-Pad4)") (class "Default")
      (node (ref "JP9") (pin "4") (pinfunction "4_4") (pintype "passive"))
    )
    (net (code "112") (name "unconnected-(JP9-Pad5)") (class "Default")
      (node (ref "JP9") (pin "5") (pinfunction "5_5") (pintype "passive"))
    )
    (net (code "113") (name "unconnected-(JP9-Pad6)") (class "Default")
      (node (ref "JP9") (pin "6") (pinfunction "6_6") (pintype "passive"))
    )
    (net (code "114") (name "unconnected-(JP9-Pad7)") (class "Default")
      (node (ref "JP9") (pin "7") (pinfunction "7_7") (pintype "passive"))
    )
    (net (code "115") (name "unconnected-(JP9-Pad8)") (class "Default")
      (node (ref "JP9") (pin "8") (pinfunction "8_8") (pintype "passive"))
    )
    (net (code "116") (name "unconnected-(JP9-Pad9)") (class "Default")
      (node (ref "JP9") (pin "9") (pinfunction "9_9") (pintype "passive"))
    )
    (net (code "117") (name "unconnected-(JP9-Pad10)") (class "Default")
      (node (ref "JP9") (pin "10") (pinfunction "10_10") (pintype "passive"))
    )
    (net (code "118") (name "unconnected-(JP9-Pad11)") (class "Default")
      (node (ref "JP9") (pin "11") (pinfunction "11_11") (pintype "passive"))
    )
    (net (code "119") (name "unconnected-(JP9-Pad12)") (class "Default")
      (node (ref "JP9") (pin "12") (pinfunction "12_12") (pintype "passive"))
    )
    (net (code "120") (name "unconnected-(JP9-Pad13)") (class "Default")
      (node (ref "JP9") (pin "13") (pinfunction "13_13") (pintype "passive"))
    )
    (net (code "121") (name "unconnected-(JP9-Pad14)") (class "Default")
      (node (ref "JP9") (pin "14") (pinfunction "14_14") (pintype "passive"))
    )
    (net (code "122") (name "unconnected-(JP9-Pad15)") (class "Default")
      (node (ref "JP9") (pin "15") (pinfunction "15_15") (pintype "passive"))
    )
    (net (code "123") (name "unconnected-(JP9-Pad16)") (class "Default")
      (node (ref "JP9") (pin "16") (pinfunction "16_16") (pintype "passive"))
    )
    (net (code "124") (name "unconnected-(JP9-Pad17)") (class "Default")
      (node (ref "JP9") (pin "17") (pinfunction "17_17") (pintype "passive"))
    )
    (net (code "125") (name "unconnected-(JP9-Pad18)") (class "Default")
      (node (ref "JP9") (pin "18") (pinfunction "18_18") (pintype "passive"))
    )
    (net (code "126") (name "unconnected-(JP10-Pad1)") (class "Default")
      (node (ref "JP10") (pin "1") (pinfunction "1_1") (pintype "passive"))
    )
    (net (code "127") (name "unconnected-(JP10-Pad2)") (class "Default")
      (node (ref "JP10") (pin "2") (pinfunction "2_2") (pintype "passive"))
    )
    (net (code "128") (name "unconnected-(JP10-Pad3)") (class "Default")
      (node (ref "JP10") (pin "3") (pinfunction "3_3") (pintype "passive"))
    )
    (net (code "129") (name "unconnected-(JP10-Pad4)") (class "Default")
      (node (ref "JP10") (pin "4") (pinfunction "4_4") (pintype "passive"))
    )
    (net (code "130") (name "unconnected-(JP10-Pad5)") (class "Default")
      (node (ref "JP10") (pin "5") (pinfunction "5_5") (pintype "passive"))
    )
    (net (code "131") (name "unconnected-(JP10-Pad6)") (class "Default")
      (node (ref "JP10") (pin "6") (pinfunction "6_6") (pintype "passive"))
    )
    (net (code "132") (name "unconnected-(JP10-Pad7)") (class "Default")
      (node (ref "JP10") (pin "7") (pinfunction "7_7") (pintype "passive"))
    )
    (net (code "133") (name "unconnected-(JP10-Pad8)") (class "Default")
      (node (ref "JP10") (pin "8") (pinfunction "8_8") (pintype "passive"))
    )
    (net (code "134") (name "unconnected-(JP10-Pad9)") (class "Default")
      (node (ref "JP10") (pin "9") (pinfunction "9_9") (pintype "passive"))
    )
    (net (code "135") (name "unconnected-(JP10-Pad10)") (class "Default")
      (node (ref "JP10") (pin "10") (pinfunction "10_10") (pintype "passive"))
    )
    (net (code "136") (name "unconnected-(JP10-Pad11)") (class "Default")
      (node (ref "JP10") (pin "11") (pinfunction "11_11") (pintype "passive"))
    )
    (net (code "137") (name "unconnected-(JP10-Pad12)") (class "Default")
      (node (ref "JP10") (pin "12") (pinfunction "12_12") (pintype "passive"))
    )
    (net (code "138") (name "unconnected-(JP10-Pad13)") (class "Default")
      (node (ref "JP10") (pin "13") (pinfunction "13_13") (pintype "passive"))
    )
    (net (code "139") (name "unconnected-(JP10-Pad14)") (class "Default")
      (node (ref "JP10") (pin "14") (pinfunction "14_14") (pintype "passive"))
    )
    (net (code "140") (name "unconnected-(JP10-Pad15)") (class "Default")
      (node (ref "JP10") (pin "15") (pinfunction "15_15") (pintype "passive"))
    )
    (net (code "141") (name "unconnected-(JP10-Pad16)") (class "Default")
      (node (ref "JP10") (pin "16") (pinfunction "16_16") (pintype "passive"))
    )
    (net (code "142") (name "unconnected-(JP10-Pad17)") (class "Default")
      (node (ref "JP10") (pin "17") (pinfunction "17_17") (pintype "passive"))
    )
    (net (code "143") (name "unconnected-(JP10-Pad18)") (class "Default")
      (node (ref "JP10") (pin "18") (pinfunction "18_18") (pintype "passive"))
    )
    (net (code "144") (name "unconnected-(JP14-Pad1)") (class "Default")
      (node (ref "JP14") (pin "1") (pinfunction "1_1") (pintype "passive"))
    )
    (net (code "145") (name "unconnected-(JP14-Pad2)") (class "Default")
      (node (ref "JP14") (pin "2") (pinfunction "2_2") (pintype "passive"))
    )
    (net (code "146") (name "unconnected-(JP14-Pad3)") (class "Default")
      (node (ref "JP14") (pin "3") (pinfunction "3_3") (pintype "passive"))
    )
    (net (code "147") (name "unconnected-(JP14-Pad4)") (class "Default")
      (node (ref "JP14") (pin "4") (pinfunction "4_4") (pintype "passive"))
    )
    (net (code "148") (name "unconnected-(JP14-Pad5)") (class "Default")
      (node (ref "JP14") (pin "5") (pinfunction "5_5") (pintype "passive"))
    )
    (net (code "149") (name "unconnected-(JP14-Pad6)") (class "Default")
      (node (ref "JP14") (pin "6") (pinfunction "6_6") (pintype "passive"))
    )
    (net (code "150") (name "unconnected-(JP14-Pad7)") (class "Default")
      (node (ref "JP14") (pin "7") (pinfunction "7_7") (pintype "passive"))
    )
    (net (code "151") (name "unconnected-(JP14-Pad8)") (class "Default")
      (node (ref "JP14") (pin "8") (pinfunction "8_8") (pintype "passive"))
    )
    (net (code "152") (name "unconnected-(JP14-Pad9)") (class "Default")
      (node (ref "JP14") (pin "9") (pinfunction "9_9") (pintype "passive"))
    )
    (net (code "153") (name "unconnected-(M1-12{slash}DIN-Pad12)") (class "Default")
      (node (ref "M1") (pin "12") (pinfunction "12/DIN_12") (pintype "bidirectional"))
    )
    (net (code "154") (name "unconnected-(M1-13{slash}SCK-Pad13)") (class "Default")
      (node (ref "M1") (pin "13") (pinfunction "13/SCK_13") (pintype "bidirectional"))
    )
    (net (code "155") (name "unconnected-(M1-PadAGND)") (class "Default")
      (node (ref "M1") (pin "AGND") (pinfunction "AGND_AGND") (pintype "power_in"))
    )
    (net (code "156") (name "unconnected-(R9-E-Pad3)") (class "Default")
      (node (ref "R9") (pin "3") (pinfunction "E_3") (pintype "passive"))
    )
    (net (code "157") (name "unconnected-(R11-E-Pad3)") (class "Default")
      (node (ref "R11") (pin "3") (pinfunction "E_3") (pintype "passive"))
    )
  )
)
